# placa_sensor2.net
KiCad netlist of a schematic drawn in EAGLE
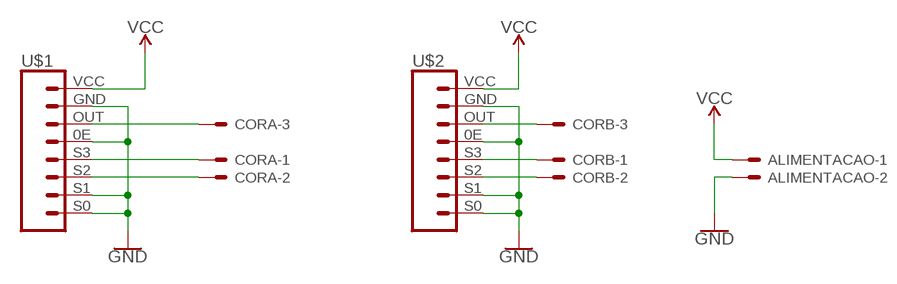
[diagram p0: schematic, sheet 1]

(export (version "E")
  (design (tool "Eeschema 10.0.6"))
  (components
    (comp (ref "ALIMENTACAO")
      (value "22-05-7028-02")
      (footprint "eagle-import:7395-02")
      (libsource (lib "eagle-import") (part "22-?-0205-7028"))
    )
    (comp (ref "CORA")
      (value "22-05-7038-03")
      (footprint "eagle-import:7395-03")
      (libsource (lib "eagle-import") (part "22-?-0305-7038"))
    )
    (comp (ref "CORB")
      (value "22-05-7038-03")
      (footprint "eagle-import:7395-03")
      (libsource (lib "eagle-import") (part "22-?-0305-7038"))
    )
    (comp (ref "U$1")
      (value "TCS3200_2TCS3200_2")
      (footprint "eagle-import:TCS3200_2")
      (libsource (lib "eagle-import") (part "TCS3200_2TCS3200_2"))
    )
    (comp (ref "U$2")
      (value "TCS3200_2TCS3200_2")
      (footprint "eagle-import:TCS3200_2")
      (libsource (lib "eagle-import") (part "TCS3200_2TCS3200_2"))
    )
  )
  (nets
    (net (code "1") (name "GND") (class "Default")
      (node (ref "ALIMENTACAO") (pin "2") (pinfunction "S_2") (pintype "passive"))
      (node (ref "U$1") (pin "0E") (pinfunction "0E_0E") (pintype "passive"))
      (node (ref "U$1") (pin "GND") (pinfunction "GND_GND") (pintype "passive"))
      (node (ref "U$1") (pin "S0") (pinfunction "S0_S0") (pintype "passive"))
      (node (ref "U$1") (pin "S1") (pinfunction "S1_S1") (pintype "passive"))
      (node (ref "U$2") (pin "0E") (pinfunction "0E_0E") (pintype "passive"))
      (node (ref "U$2") (pin "GND") (pinfunction "GND_GND") (pintype "passive"))
      (node (ref "U$2") (pin "S0") (pinfunction "S0_S0") (pintype "passive"))
      (node (ref "U$2") (pin "S1") (pinfunction "S1_S1") (pintype "passive"))
    )
    (net (code "2") (name "Net-(CORAA-S)") (class "Default")
      (node (ref "CORA") (pin "1") (pinfunction "S_1") (pintype "passive"))
      (node (ref "U$1") (pin "S3") (pinfunction "S3_S3") (pintype "passive"))
    )
    (net (code "3") (name "Net-(CORAB-S)") (class "Default")
      (node (ref "CORA") (pin "2") (pinfunction "S_2") (pintype "passive"))
      (node (ref "U$1") (pin "S2") (pinfunction "S2_S2") (pintype "passive"))
    )
    (net (code "4") (name "Net-(CORAC-S)") (class "Default")
      (node (ref "CORA") (pin "3") (pinfunction "S_3") (pintype "passive"))
      (node (ref "U$1") (pin "OUT") (pinfunction "OUT_OUT") (pintype "passive"))
    )
    (net (code "5") (name "Net-(CORBA-S)") (class "Default")
      (node (ref "CORB") (pin "1") (pinfunction "S_1") (pintype "passive"))
      (node (ref "U$2") (pin "S3") (pinfunction "S3_S3") (pintype "passive"))
    )
    (net (code "6") (name "Net-(CORBB-S)") (class "Default")
      (node (ref "CORB") (pin "2") (pinfunction "S_2") (pintype "passive"))
      (node (ref "U$2") (pin "S2") (pinfunction "S2_S2") (pintype "passive"))
    )
    (net (code "7") (name "Net-(CORBC-S)") (class "Default")
      (node (ref "CORB") (pin "3") (pinfunction "S_3") (pintype "passive"))
      (node (ref "U$2") (pin "OUT") (pinfunction "OUT_OUT") (pintype "passive"))
    )
    (net (code "8") (name "VCC") (class "Default")
      (node (ref "ALIMENTACAO") (pin "1") (pinfunction "S_1") (pintype "passive"))
      (node (ref "U$1") (pin "VCC") (pinfunction "VCC_VCC") (pintype "passive"))
      (node (ref "U$2") (pin "VCC") (pinfunction "VCC_VCC") (pintype "passive"))
    )
  )
)
